# megaduck.net
KiCad netlist of a schematic drawn in EasyEDA Pro
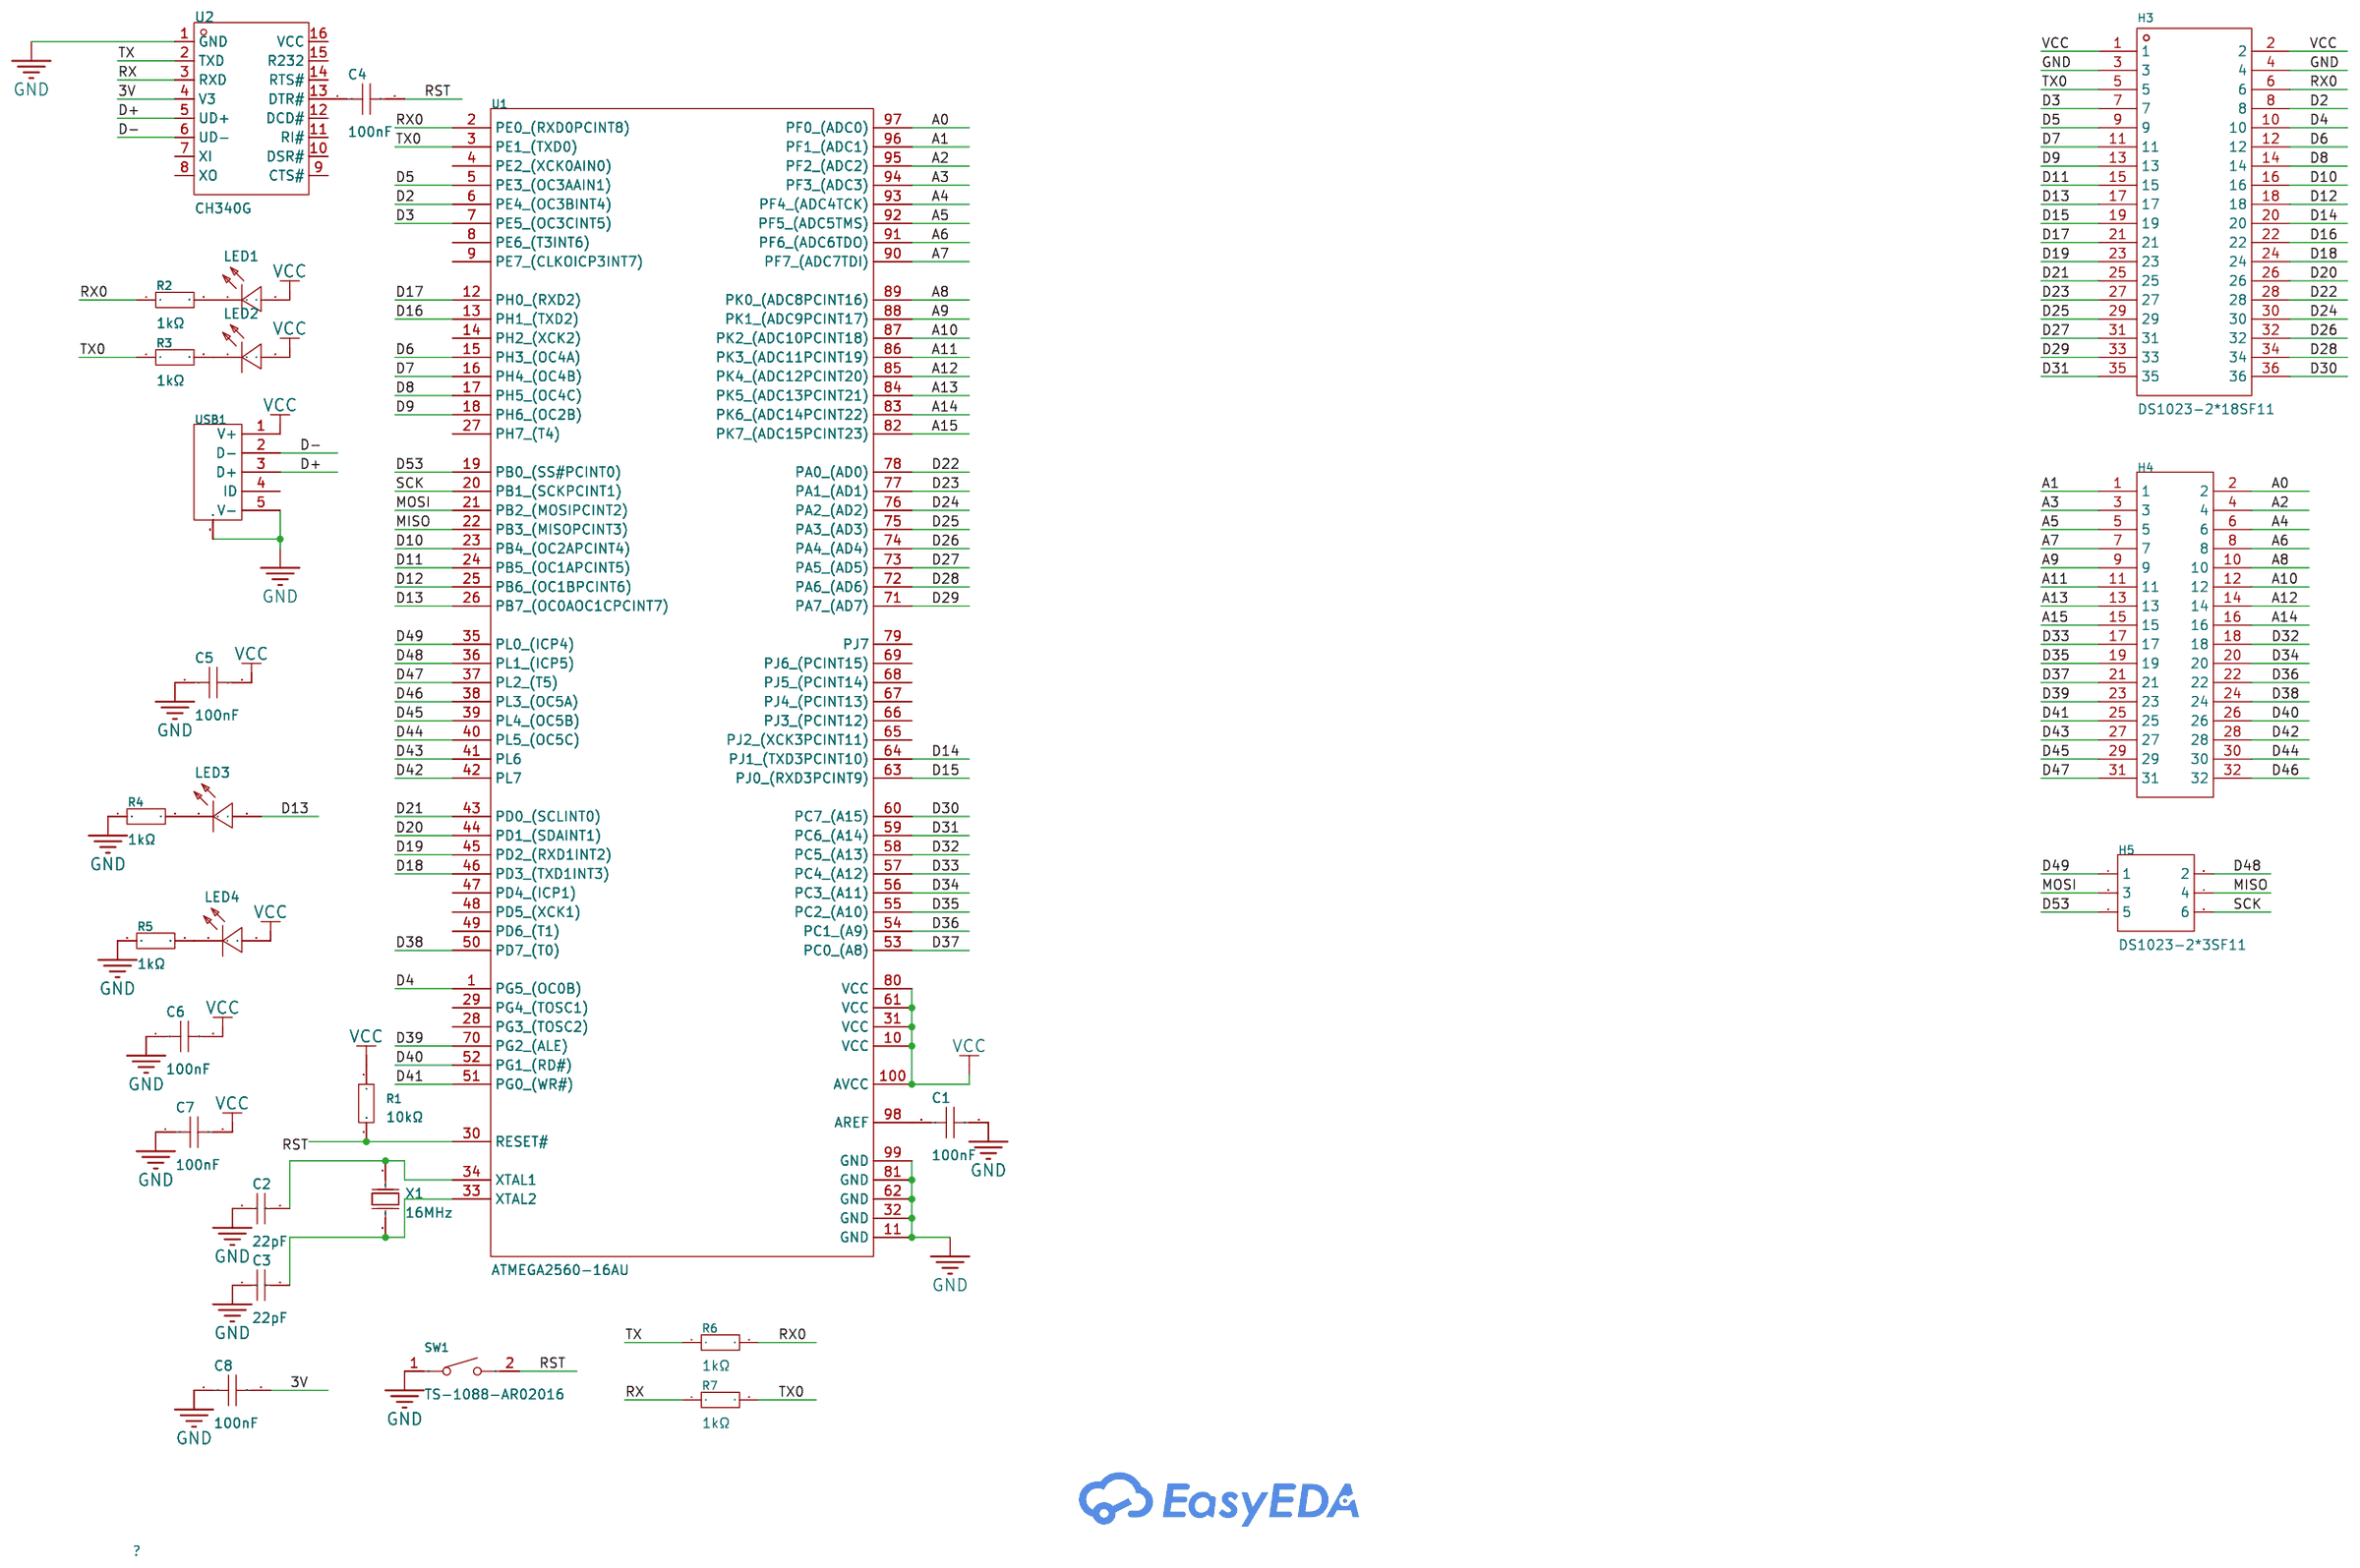
[diagram p0: schematic sheet]

(export (version "E")
  (design (tool "Eeschema 10.0.6"))
  (components
    (comp (ref "C1")
      (value "100nF")
      (footprint "easyedapro:C0402")
      (fields
        (field (name "Manufacturer Part") "CL05B104KO5NNNC")
        (field (name "Manufacturer") "SAMSUNG(三星)")
      )
      (libsource (lib "easyedapro") (part "CL05B104KO5NNNC"))
    )
    (comp (ref "C2")
      (value "22pF")
      (footprint "easyedapro:C0402")
      (fields (field (name "Manufacturer Part") "0402CG220J500NT") (field (name "Manufacturer") "FH(风华)"))
      (libsource (lib "easyedapro") (part "0402CG220J500NT"))
    )
    (comp (ref "C3")
      (value "22pF")
      (footprint "easyedapro:C0402")
      (fields (field (name "Manufacturer Part") "0402CG220J500NT") (field (name "Manufacturer") "FH(风华)"))
      (libsource (lib "easyedapro") (part "0402CG220J500NT"))
    )
    (comp (ref "C4")
      (value "100nF")
      (footprint "easyedapro:C0402")
      (fields
        (field (name "Manufacturer Part") "CL05B104KO5NNNC")
        (field (name "Manufacturer") "SAMSUNG(三星)")
      )
      (libsource (lib "easyedapro") (part "CL05B104KO5NNNC"))
    )
    (comp (ref "C5")
      (value "100nF")
      (footprint "easyedapro:C0402")
      (fields
        (field (name "Manufacturer Part") "CL05B104KO5NNNC")
        (field (name "Manufacturer") "SAMSUNG(三星)")
      )
      (libsource (lib "easyedapro") (part "CL05B104KO5NNNC"))
    )
    (comp (ref "C6")
      (value "100nF")
      (footprint "easyedapro:C0402")
      (fields
        (field (name "Manufacturer Part") "CL05B104KO5NNNC")
        (field (name "Manufacturer") "SAMSUNG(三星)")
      )
      (libsource (lib "easyedapro") (part "CL05B104KO5NNNC"))
    )
    (comp (ref "C7")
      (value "100nF")
      (footprint "easyedapro:C0402")
      (fields
        (field (name "Manufacturer Part") "CL05B104KO5NNNC")
        (field (name "Manufacturer") "SAMSUNG(三星)")
      )
      (libsource (lib "easyedapro") (part "CL05B104KO5NNNC"))
    )
    (comp (ref "C8")
      (value "100nF")
      (footprint "easyedapro:C0402")
      (fields
        (field (name "Manufacturer Part") "CL05B104KO5NNNC")
        (field (name "Manufacturer") "SAMSUNG(三星)")
      )
      (libsource (lib "easyedapro") (part "CL05B104KO5NNNC"))
    )
    (comp (ref "H3")
      (value "DS1023-2*18SF11")
      (footprint "easyedapro:HDR-TH_36P-P2.54-V-F-R2-C18-S2.54-1")
      (fields (field (name "Manufacturer") "CONNFLY"))
      (libsource (lib "easyedapro") (part "DS1023-2*18SF11"))
    )
    (comp (ref "H4")
      (value "DS1023-2*16SF11")
      (footprint "easyedapro:HDR-TH_32P-P2.54-V-F-R2-C16-S2.54-1")
      (fields (field (name "Manufacturer") "CONNFLY"))
      (libsource (lib "easyedapro") (part "DS1023-2*16SF11"))
    )
    (comp (ref "H5")
      (value "DS1023-2*3SF11")
      (footprint "easyedapro:HDR-TH_6P-P2.54-V-F-R2-C3-S2.54")
      (fields (field (name "Manufacturer") "CONNFLY"))
      (libsource (lib "easyedapro") (part "Header-Female-2.54_2x3"))
    )
    (comp (ref "LED1")
      (value "KT-0603R")
      (footprint "easyedapro:LED0603-RD")
      (fields (field (name "Manufacturer") "KENTO"))
      (libsource (lib "easyedapro") (part "KT-0603R"))
    )
    (comp (ref "LED2")
      (value "KT-0603R")
      (footprint "easyedapro:LED0603-RD")
      (fields (field (name "Manufacturer") "KENTO"))
      (libsource (lib "easyedapro") (part "KT-0603R"))
    )
    (comp (ref "LED3")
      (value "KT-0603R")
      (footprint "easyedapro:LED0603-RD")
      (fields (field (name "Manufacturer") "KENTO"))
      (libsource (lib "easyedapro") (part "KT-0603R"))
    )
    (comp (ref "LED4")
      (value "KT-0603R")
      (footprint "easyedapro:LED0603-RD")
      (fields (field (name "Manufacturer") "KENTO"))
      (libsource (lib "easyedapro") (part "KT-0603R"))
    )
    (comp (ref "R1")
      (value "10kΩ")
      (footprint "easyedapro:R1206")
      (fields
        (field (name "Manufacturer Part") "1206W4J0103T5E")
        (field (name "Manufacturer") "UNI-ROYAL(厚声)")
      )
      (libsource (lib "easyedapro") (part "1206W4J0103T5E"))
    )
    (comp (ref "R2")
      (value "1kΩ")
      (footprint "easyedapro:R1206")
      (fields
        (field (name "Manufacturer Part") "1206W4F1001T5E")
        (field (name "Manufacturer") "UNI-ROYAL(厚声)")
      )
      (libsource (lib "easyedapro") (part "1206W4F1001T5E"))
    )
    (comp (ref "R3")
      (value "1kΩ")
      (footprint "easyedapro:R1206")
      (fields
        (field (name "Manufacturer Part") "1206W4F1001T5E")
        (field (name "Manufacturer") "UNI-ROYAL(厚声)")
      )
      (libsource (lib "easyedapro") (part "1206W4F1001T5E"))
    )
    (comp (ref "R4")
      (value "1kΩ")
      (footprint "easyedapro:R1206")
      (fields
        (field (name "Manufacturer Part") "1206W4F1001T5E")
        (field (name "Manufacturer") "UNI-ROYAL(厚声)")
      )
      (libsource (lib "easyedapro") (part "1206W4F1001T5E"))
    )
    (comp (ref "R5")
      (value "1kΩ")
      (footprint "easyedapro:R1206")
      (fields
        (field (name "Manufacturer Part") "1206W4F1001T5E")
        (field (name "Manufacturer") "UNI-ROYAL(厚声)")
      )
      (libsource (lib "easyedapro") (part "1206W4F1001T5E"))
    )
    (comp (ref "R6")
      (value "1kΩ")
      (footprint "easyedapro:R1206")
      (fields
        (field (name "Manufacturer Part") "1206W4F1001T5E")
        (field (name "Manufacturer") "UNI-ROYAL(厚声)")
      )
      (libsource (lib "easyedapro") (part "1206W4F1001T5E"))
    )
    (comp (ref "R7")
      (value "1kΩ")
      (footprint "easyedapro:R1206")
      (fields
        (field (name "Manufacturer Part") "1206W4F1001T5E")
        (field (name "Manufacturer") "UNI-ROYAL(厚声)")
      )
      (libsource (lib "easyedapro") (part "1206W4F1001T5E"))
    )
    (comp (ref "SW1")
      (value "TS-1088-AR02016")
      (footprint "easyedapro:SW-SMD_L3.9-W3.0-P4.45")
      (fields (field (name "Manufacturer") "XUNPU(讯普)"))
      (libsource (lib "easyedapro") (part "TS-1088-AR02016"))
    )
    (comp (ref "U1")
      (value "ATMEGA2560-16AU")
      (footprint "easyedapro:TQFP-100_L14.0-W14.0-P0.50-LS16.0-BL")
      (fields (field (name "Manufacturer") "MICROCHIP(美国微芯)"))
      (libsource (lib "easyedapro") (part "ATMEGA2560-16AU"))
    )
    (comp (ref "U2")
      (value "CH340G")
      (footprint "easyedapro:SOIC-16_L9.9-W3.9-P1.27-LS6.0-BL")
      (fields (field (name "Manufacturer") "WCH(南京沁恒)"))
      (libsource (lib "easyedapro") (part "CH340G"))
    )
    (comp (ref "USB1")
      (value "920-E52A2021S10100")
      (footprint "easyedapro:MICRO-USB-SMD_5P-P0.65-H-F_C10418")
      (fields (field (name "Manufacturer") "精拓金"))
      (libsource (lib "easyedapro") (part "micro USBFemale"))
    )
    (comp (ref "X1")
      (value "16MHz")
      (footprint "easyedapro:HC-49S_L11.4-W4.8")
      (fields (field (name "Manufacturer Part") "X49SM16MSD2SC") (field (name "Manufacturer") "YXC(扬兴晶振)"))
      (libsource (lib "easyedapro") (part "X49SM16MSD2SC"))
    )
  )
  (nets
    (net (code "1") (name "/3V") (class "Default")
      (node (ref "C8") (pin "2") (pinfunction "2_2") (pintype "unspecified"))
      (node (ref "U2") (pin "4") (pinfunction "V3_4") (pintype "unspecified"))
    )
    (net (code "2") (name "/A0") (class "Default")
      (node (ref "H4") (pin "2") (pinfunction "2_2") (pintype "input"))
      (node (ref "U1") (pin "97") (pinfunction "PF0_(ADC0)_97") (pintype "bidirectional"))
    )
    (net (code "3") (name "/A1") (class "Default")
      (node (ref "H4") (pin "1") (pinfunction "1_1") (pintype "input"))
      (node (ref "U1") (pin "96") (pinfunction "PF1_(ADC1)_96") (pintype "bidirectional"))
    )
    (net (code "4") (name "/A2") (class "Default")
      (node (ref "H4") (pin "4") (pinfunction "4_4") (pintype "input"))
      (node (ref "U1") (pin "95") (pinfunction "PF2_(ADC2)_95") (pintype "bidirectional"))
    )
    (net (code "5") (name "/A3") (class "Default")
      (node (ref "H4") (pin "3") (pinfunction "3_3") (pintype "input"))
      (node (ref "U1") (pin "94") (pinfunction "PF3_(ADC3)_94") (pintype "bidirectional"))
    )
    (net (code "6") (name "/A4") (class "Default")
      (node (ref "H4") (pin "6") (pinfunction "6_6") (pintype "input"))
      (node (ref "U1") (pin "93") (pinfunction "PF4_(ADC4TCK)_93") (pintype "bidirectional"))
    )
    (net (code "7") (name "/A5") (class "Default")
      (node (ref "H4") (pin "5") (pinfunction "5_5") (pintype "input"))
      (node (ref "U1") (pin "92") (pinfunction "PF5_(ADC5TMS)_92") (pintype "bidirectional"))
    )
    (net (code "8") (name "/A6") (class "Default")
      (node (ref "H4") (pin "8") (pinfunction "8_8") (pintype "input"))
      (node (ref "U1") (pin "91") (pinfunction "PF6_(ADC6TDO)_91") (pintype "bidirectional"))
    )
    (net (code "9") (name "/A7") (class "Default")
      (node (ref "H4") (pin "7") (pinfunction "7_7") (pintype "input"))
      (node (ref "U1") (pin "90") (pinfunction "PF7_(ADC7TDI)_90") (pintype "bidirectional"))
    )
    (net (code "10") (name "/A8") (class "Default")
      (node (ref "H4") (pin "10") (pinfunction "10_10") (pintype "input"))
      (node (ref "U1") (pin "89") (pinfunction "PK0_(ADC8PCINT16)_89") (pintype "bidirectional"))
    )
    (net (code "11") (name "/A9") (class "Default")
      (node (ref "H4") (pin "9") (pinfunction "9_9") (pintype "input"))
      (node (ref "U1") (pin "88") (pinfunction "PK1_(ADC9PCINT17)_88") (pintype "bidirectional"))
    )
    (net (code "12") (name "/A10") (class "Default")
      (node (ref "H4") (pin "12") (pinfunction "12_12") (pintype "input"))
      (node (ref "U1") (pin "87") (pinfunction "PK2_(ADC10PCINT18)_87") (pintype "bidirectional"))
    )
    (net (code "13") (name "/A11") (class "Default")
      (node (ref "H4") (pin "11") (pinfunction "11_11") (pintype "input"))
      (node (ref "U1") (pin "86") (pinfunction "PK3_(ADC11PCINT19)_86") (pintype "bidirectional"))
    )
    (net (code "14") (name "/A12") (class "Default")
      (node (ref "H4") (pin "14") (pinfunction "14_14") (pintype "input"))
      (node (ref "U1") (pin "85") (pinfunction "PK4_(ADC12PCINT20)_85") (pintype "bidirectional"))
    )
    (net (code "15") (name "/A13") (class "Default")
      (node (ref "H4") (pin "13") (pinfunction "13_13") (pintype "input"))
      (node (ref "U1") (pin "84") (pinfunction "PK5_(ADC13PCINT21)_84") (pintype "bidirectional"))
    )
    (net (code "16") (name "/A14") (class "Default")
      (node (ref "H4") (pin "16") (pinfunction "16_16") (pintype "input"))
      (node (ref "U1") (pin "83") (pinfunction "PK6_(ADC14PCINT22)_83") (pintype "bidirectional"))
    )
    (net (code "17") (name "/A15") (class "Default")
      (node (ref "H4") (pin "15") (pinfunction "15_15") (pintype "input"))
      (node (ref "U1") (pin "82") (pinfunction "PK7_(ADC15PCINT23)_82") (pintype "bidirectional"))
    )
    (net (code "18") (name "/D+") (class "Default")
      (node (ref "U2") (pin "5") (pinfunction "UD+_5") (pintype "unspecified"))
      (node (ref "USB1") (pin "3") (pinfunction "D+_3") (pintype "input"))
    )
    (net (code "19") (name "/D-") (class "Default")
      (node (ref "U2") (pin "6") (pinfunction "UD-_6") (pintype "unspecified"))
      (node (ref "USB1") (pin "2") (pinfunction "D-_2") (pintype "input"))
    )
    (net (code "20") (name "/D2") (class "Default")
      (node (ref "H3") (pin "8") (pinfunction "8_8") (pintype "input"))
      (node (ref "U1") (pin "6") (pinfunction "PE4_(OC3BINT4)_6") (pintype "bidirectional"))
    )
    (net (code "21") (name "/D3") (class "Default")
      (node (ref "H3") (pin "7") (pinfunction "7_7") (pintype "input"))
      (node (ref "U1") (pin "7") (pinfunction "PE5_(OC3CINT5)_7") (pintype "bidirectional"))
    )
    (net (code "22") (name "/D4") (class "Default")
      (node (ref "H3") (pin "10") (pinfunction "10_10") (pintype "input"))
      (node (ref "U1") (pin "1") (pinfunction "PG5_(OC0B)_1") (pintype "bidirectional"))
    )
    (net (code "23") (name "/D5") (class "Default")
      (node (ref "H3") (pin "9") (pinfunction "9_9") (pintype "input"))
      (node (ref "U1") (pin "5") (pinfunction "PE3_(OC3AAIN1)_5") (pintype "bidirectional"))
    )
    (net (code "24") (name "/D6") (class "Default")
      (node (ref "H3") (pin "12") (pinfunction "12_12") (pintype "input"))
      (node (ref "U1") (pin "15") (pinfunction "PH3_(OC4A)_15") (pintype "bidirectional"))
    )
    (net (code "25") (name "/D7") (class "Default")
      (node (ref "H3") (pin "11") (pinfunction "11_11") (pintype "input"))
      (node (ref "U1") (pin "16") (pinfunction "PH4_(OC4B)_16") (pintype "bidirectional"))
    )
    (net (code "26") (name "/D8") (class "Default")
      (node (ref "H3") (pin "14") (pinfunction "14_14") (pintype "input"))
      (node (ref "U1") (pin "17") (pinfunction "PH5_(OC4C)_17") (pintype "bidirectional"))
    )
    (net (code "27") (name "/D9") (class "Default")
      (node (ref "H3") (pin "13") (pinfunction "13_13") (pintype "input"))
      (node (ref "U1") (pin "18") (pinfunction "PH6_(OC2B)_18") (pintype "bidirectional"))
    )
    (net (code "28") (name "/D10") (class "Default")
      (node (ref "H3") (pin "16") (pinfunction "16_16") (pintype "input"))
      (node (ref "U1") (pin "23") (pinfunction "PB4_(OC2APCINT4)_23") (pintype "bidirectional"))
    )
    (net (code "29") (name "/D11") (class "Default")
      (node (ref "H3") (pin "15") (pinfunction "15_15") (pintype "input"))
      (node (ref "U1") (pin "24") (pinfunction "PB5_(OC1APCINT5)_24") (pintype "bidirectional"))
    )
    (net (code "30") (name "/D12") (class "Default")
      (node (ref "H3") (pin "18") (pinfunction "18_18") (pintype "input"))
      (node (ref "U1") (pin "25") (pinfunction "PB6_(OC1BPCINT6)_25") (pintype "bidirectional"))
    )
    (net (code "31") (name "/D13") (class "Default")
      (node (ref "H3") (pin "17") (pinfunction "17_17") (pintype "input"))
      (node (ref "LED3") (pin "2") (pinfunction "A_2") (pintype "unspecified"))
      (node (ref "U1") (pin "26") (pinfunction "PB7_(OC0AOC1CPCINT7)_26") (pintype "bidirectional"))
    )
    (net (code "32") (name "/D14") (class "Default")
      (node (ref "H3") (pin "20") (pinfunction "20_20") (pintype "input"))
      (node (ref "U1") (pin "64") (pinfunction "PJ1_(TXD3PCINT10)_64") (pintype "bidirectional"))
    )
    (net (code "33") (name "/D15") (class "Default")
      (node (ref "H3") (pin "19") (pinfunction "19_19") (pintype "input"))
      (node (ref "U1") (pin "63") (pinfunction "PJ0_(RXD3PCINT9)_63") (pintype "bidirectional"))
    )
    (net (code "34") (name "/D16") (class "Default")
      (node (ref "H3") (pin "22") (pinfunction "22_22") (pintype "input"))
      (node (ref "U1") (pin "13") (pinfunction "PH1_(TXD2)_13") (pintype "bidirectional"))
    )
    (net (code "35") (name "/D17") (class "Default")
      (node (ref "H3") (pin "21") (pinfunction "21_21") (pintype "input"))
      (node (ref "U1") (pin "12") (pinfunction "PH0_(RXD2)_12") (pintype "bidirectional"))
    )
    (net (code "36") (name "/D18") (class "Default")
      (node (ref "H3") (pin "24") (pinfunction "24_24") (pintype "input"))
      (node (ref "U1") (pin "46") (pinfunction "PD3_(TXD1INT3)_46") (pintype "bidirectional"))
    )
    (net (code "37") (name "/D19") (class "Default")
      (node (ref "H3") (pin "23") (pinfunction "23_23") (pintype "input"))
      (node (ref "U1") (pin "45") (pinfunction "PD2_(RXD1INT2)_45") (pintype "bidirectional"))
    )
    (net (code "38") (name "/D20") (class "Default")
      (node (ref "H3") (pin "26") (pinfunction "26_26") (pintype "input"))
      (node (ref "U1") (pin "44") (pinfunction "PD1_(SDAINT1)_44") (pintype "bidirectional"))
    )
    (net (code "39") (name "/D21") (class "Default")
      (node (ref "H3") (pin "25") (pinfunction "25_25") (pintype "input"))
      (node (ref "U1") (pin "43") (pinfunction "PD0_(SCLINT0)_43") (pintype "bidirectional"))
    )
    (net (code "40") (name "/D22") (class "Default")
      (node (ref "H3") (pin "28") (pinfunction "28_28") (pintype "input"))
      (node (ref "U1") (pin "78") (pinfunction "PA0_(AD0)_78") (pintype "bidirectional"))
    )
    (net (code "41") (name "/D23") (class "Default")
      (node (ref "H3") (pin "27") (pinfunction "27_27") (pintype "input"))
      (node (ref "U1") (pin "77") (pinfunction "PA1_(AD1)_77") (pintype "bidirectional"))
    )
    (net (code "42") (name "/D24") (class "Default")
      (node (ref "H3") (pin "30") (pinfunction "30_30") (pintype "input"))
      (node (ref "U1") (pin "76") (pinfunction "PA2_(AD2)_76") (pintype "bidirectional"))
    )
    (net (code "43") (name "/D25") (class "Default")
      (node (ref "H3") (pin "29") (pinfunction "29_29") (pintype "input"))
      (node (ref "U1") (pin "75") (pinfunction "PA3_(AD3)_75") (pintype "bidirectional"))
    )
    (net (code "44") (name "/D26") (class "Default")
      (node (ref "H3") (pin "32") (pinfunction "32_32") (pintype "input"))
      (node (ref "U1") (pin "74") (pinfunction "PA4_(AD4)_74") (pintype "bidirectional"))
    )
    (net (code "45") (name "/D27") (class "Default")
      (node (ref "H3") (pin "31") (pinfunction "31_31") (pintype "input"))
      (node (ref "U1") (pin "73") (pinfunction "PA5_(AD5)_73") (pintype "bidirectional"))
    )
    (net (code "46") (name "/D28") (class "Default")
      (node (ref "H3") (pin "34") (pinfunction "34_34") (pintype "input"))
      (node (ref "U1") (pin "72") (pinfunction "PA6_(AD6)_72") (pintype "bidirectional"))
    )
    (net (code "47") (name "/D29") (class "Default")
      (node (ref "H3") (pin "33") (pinfunction "33_33") (pintype "input"))
      (node (ref "U1") (pin "71") (pinfunction "PA7_(AD7)_71") (pintype "bidirectional"))
    )
    (net (code "48") (name "/D30") (class "Default")
      (node (ref "H3") (pin "36") (pinfunction "36_36") (pintype "input"))
      (node (ref "U1") (pin "60") (pinfunction "PC7_(A15)_60") (pintype "bidirectional"))
    )
    (net (code "49") (name "/D31") (class "Default")
      (node (ref "H3") (pin "35") (pinfunction "35_35") (pintype "input"))
      (node (ref "U1") (pin "59") (pinfunction "PC6_(A14)_59") (pintype "bidirectional"))
    )
    (net (code "50") (name "/D32") (class "Default")
      (node (ref "H4") (pin "18") (pinfunction "18_18") (pintype "input"))
      (node (ref "U1") (pin "58") (pinfunction "PC5_(A13)_58") (pintype "bidirectional"))
    )
    (net (code "51") (name "/D33") (class "Default")
      (node (ref "H4") (pin "17") (pinfunction "17_17") (pintype "input"))
      (node (ref "U1") (pin "57") (pinfunction "PC4_(A12)_57") (pintype "bidirectional"))
    )
    (net (code "52") (name "/D34") (class "Default")
      (node (ref "H4") (pin "20") (pinfunction "20_20") (pintype "input"))
      (node (ref "U1") (pin "56") (pinfunction "PC3_(A11)_56") (pintype "bidirectional"))
    )
    (net (code "53") (name "/D35") (class "Default")
      (node (ref "H4") (pin "19") (pinfunction "19_19") (pintype "input"))
      (node (ref "U1") (pin "55") (pinfunction "PC2_(A10)_55") (pintype "bidirectional"))
    )
    (net (code "54") (name "/D36") (class "Default")
      (node (ref "H4") (pin "22") (pinfunction "22_22") (pintype "input"))
      (node (ref "U1") (pin "54") (pinfunction "PC1_(A9)_54") (pintype "bidirectional"))
    )
    (net (code "55") (name "/D37") (class "Default")
      (node (ref "H4") (pin "21") (pinfunction "21_21") (pintype "input"))
      (node (ref "U1") (pin "53") (pinfunction "PC0_(A8)_53") (pintype "bidirectional"))
    )
    (net (code "56") (name "/D38") (class "Default")
      (node (ref "H4") (pin "24") (pinfunction "24_24") (pintype "input"))
      (node (ref "U1") (pin "50") (pinfunction "PD7_(T0)_50") (pintype "bidirectional"))
    )
    (net (code "57") (name "/D39") (class "Default")
      (node (ref "H4") (pin "23") (pinfunction "23_23") (pintype "input"))
      (node (ref "U1") (pin "70") (pinfunction "PG2_(ALE)_70") (pintype "bidirectional"))
    )
    (net (code "58") (name "/D40") (class "Default")
      (node (ref "H4") (pin "26") (pinfunction "26_26") (pintype "input"))
      (node (ref "U1") (pin "52") (pinfunction "PG1_(RD#)_52") (pintype "bidirectional"))
    )
    (net (code "59") (name "/D41") (class "Default")
      (node (ref "H4") (pin "25") (pinfunction "25_25") (pintype "input"))
      (node (ref "U1") (pin "51") (pinfunction "PG0_(WR#)_51") (pintype "bidirectional"))
    )
    (net (code "60") (name "/D42") (class "Default")
      (node (ref "H4") (pin "28") (pinfunction "28_28") (pintype "input"))
      (node (ref "U1") (pin "42") (pinfunction "PL7_42") (pintype "bidirectional"))
    )
    (net (code "61") (name "/D43") (class "Default")
      (node (ref "H4") (pin "27") (pinfunction "27_27") (pintype "input"))
      (node (ref "U1") (pin "41") (pinfunction "PL6_41") (pintype "bidirectional"))
    )
    (net (code "62") (name "/D44") (class "Default")
      (node (ref "H4") (pin "30") (pinfunction "30_30") (pintype "input"))
      (node (ref "U1") (pin "40") (pinfunction "PL5_(OC5C)_40") (pintype "bidirectional"))
    )
    (net (code "63") (name "/D45") (class "Default")
      (node (ref "H4") (pin "29") (pinfunction "29_29") (pintype "input"))
      (node (ref "U1") (pin "39") (pinfunction "PL4_(OC5B)_39") (pintype "bidirectional"))
    )
    (net (code "64") (name "/D46") (class "Default")
      (node (ref "H4") (pin "32") (pinfunction "32_32") (pintype "input"))
      (node (ref "U1") (pin "38") (pinfunction "PL3_(OC5A)_38") (pintype "bidirectional"))
    )
    (net (code "65") (name "/D47") (class "Default")
      (node (ref "H4") (pin "31") (pinfunction "31_31") (pintype "input"))
      (node (ref "U1") (pin "37") (pinfunction "PL2_(T5)_37") (pintype "bidirectional"))
    )
    (net (code "66") (name "/D48") (class "Default")
      (node (ref "H5") (pin "2") (pinfunction "2_2") (pintype "input"))
      (node (ref "U1") (pin "36") (pinfunction "PL1_(ICP5)_36") (pintype "bidirectional"))
    )
    (net (code "67") (name "/D49") (class "Default")
      (node (ref "H5") (pin "1") (pinfunction "1_1") (pintype "input"))
      (node (ref "U1") (pin "35") (pinfunction "PL0_(ICP4)_35") (pintype "bidirectional"))
    )
    (net (code "68") (name "/D53") (class "Default")
      (node (ref "H5") (pin "5") (pinfunction "5_5") (pintype "input"))
      (node (ref "U1") (pin "19") (pinfunction "PB0_(SS#PCINT0)_19") (pintype "bidirectional"))
    )
    (net (code "69") (name "/MISO") (class "Default")
      (node (ref "H5") (pin "4") (pinfunction "4_4") (pintype "input"))
      (node (ref "U1") (pin "22") (pinfunction "PB3_(MISOPCINT3)_22") (pintype "bidirectional"))
    )
    (net (code "70") (name "/MOSI") (class "Default")
      (node (ref "H5") (pin "3") (pinfunction "3_3") (pintype "input"))
      (node (ref "U1") (pin "21") (pinfunction "PB2_(MOSIPCINT2)_21") (pintype "bidirectional"))
    )
    (net (code "71") (name "/RST") (class "Default")
      (node (ref "C4") (pin "2") (pinfunction "2_2") (pintype "unspecified"))
      (node (ref "R1") (pin "2") (pinfunction "2_2") (pintype "input"))
      (node (ref "SW1") (pin "2") (pinfunction "2_2") (pintype "input"))
      (node (ref "U1") (pin "30") (pinfunction "RESET#_30") (pintype "input"))
    )
    (net (code "72") (name "/RX") (class "Default")
      (node (ref "R7") (pin "1") (pinfunction "1_1") (pintype "input"))
      (node (ref "U2") (pin "3") (pinfunction "RXD_3") (pintype "unspecified"))
    )
    (net (code "73") (name "/RX0") (class "Default")
      (node (ref "H3") (pin "6") (pinfunction "6_6") (pintype "input"))
      (node (ref "R2") (pin "1") (pinfunction "1_1") (pintype "input"))
      (node (ref "R6") (pin "2") (pinfunction "2_2") (pintype "input"))
      (node (ref "U1") (pin "2") (pinfunction "PE0_(RXD0PCINT8)_2") (pintype "bidirectional"))
    )
    (net (code "74") (name "/SCK") (class "Default")
      (node (ref "H5") (pin "6") (pinfunction "6_6") (pintype "input"))
      (node (ref "U1") (pin "20") (pinfunction "PB1_(SCKPCINT1)_20") (pintype "bidirectional"))
    )
    (net (code "75") (name "/TX") (class "Default")
      (node (ref "R6") (pin "1") (pinfunction "1_1") (pintype "input"))
      (node (ref "U2") (pin "2") (pinfunction "TXD_2") (pintype "unspecified"))
    )
    (net (code "76") (name "/TX0") (class "Default")
      (node (ref "H3") (pin "5") (pinfunction "5_5") (pintype "input"))
      (node (ref "R3") (pin "1") (pinfunction "1_1") (pintype "input"))
      (node (ref "R7") (pin "2") (pinfunction "2_2") (pintype "input"))
      (node (ref "U1") (pin "3") (pinfunction "PE1_(TXD0)_3") (pintype "bidirectional"))
    )
    (net (code "77") (name "GND") (class "Default")
      (node (ref "C1") (pin "2") (pinfunction "2_2") (pintype "unspecified"))
      (node (ref "C2") (pin "1") (pinfunction "1_1") (pintype "input"))
      (node (ref "C3") (pin "1") (pinfunction "1_1") (pintype "input"))
      (node (ref "C5") (pin "1") (pinfunction "1_1") (pintype "unspecified"))
      (node (ref "C6") (pin "1") (pinfunction "1_1") (pintype "unspecified"))
      (node (ref "C7") (pin "1") (pinfunction "1_1") (pintype "unspecified"))
      (node (ref "C8") (pin "1") (pinfunction "1_1") (pintype "unspecified"))
      (node (ref "H3") (pin "3") (pinfunction "3_3") (pintype "input"))
      (node (ref "H3") (pin "4") (pinfunction "4_4") (pintype "input"))
      (node (ref "R4") (pin "1") (pinfunction "1_1") (pintype "input"))
      (node (ref "R5") (pin "1") (pinfunction "1_1") (pintype "input"))
      (node (ref "SW1") (pin "1") (pinfunction "1_1") (pintype "input"))
      (node (ref "U1") (pin "11") (pinfunction "GND_11") (pintype "input"))
      (node (ref "U1") (pin "32") (pinfunction "GND_32") (pintype "input"))
      (node (ref "U1") (pin "62") (pinfunction "GND_62") (pintype "input"))
      (node (ref "U1") (pin "81") (pinfunction "GND_81") (pintype "input"))
      (node (ref "U1") (pin "99") (pinfunction "GND_99") (pintype "input"))
      (node (ref "U2") (pin "1") (pinfunction "GND_1") (pintype "unspecified"))
      (node (ref "USB1") (pin "5") (pinfunction "V-_5") (pintype "input"))
      (node (ref "USB1") (pin "SH0") (pinfunction "MTN_SH0") (pintype "input"))
      (node (ref "USB1") (pin "SH1") (pinfunction "1_SH1") (pintype "input"))
      (node (ref "USB1") (pin "SH2") (pinfunction "2_SH2") (pintype "input"))
      (node (ref "USB1") (pin "SH3") (pinfunction "3_SH3") (pintype "input"))
    )
    (net (code "78") (name "Net-(LED1-K)") (class "Default")
      (node (ref "LED1") (pin "1") (pinfunction "K_1") (pintype "unspecified"))
      (node (ref "R2") (pin "2") (pinfunction "2_2") (pintype "input"))
    )
    (net (code "79") (name "Net-(LED2-K)") (class "Default")
      (node (ref "LED2") (pin "1") (pinfunction "K_1") (pintype "unspecified"))
      (node (ref "R3") (pin "2") (pinfunction "2_2") (pintype "input"))
    )
    (net (code "80") (name "Net-(LED3-K)") (class "Default")
      (node (ref "LED3") (pin "1") (pinfunction "K_1") (pintype "unspecified"))
      (node (ref "R4") (pin "2") (pinfunction "2_2") (pintype "input"))
    )
    (net (code "81") (name "Net-(LED4-K)") (class "Default")
      (node (ref "LED4") (pin "1") (pinfunction "K_1") (pintype "unspecified"))
      (node (ref "R5") (pin "2") (pinfunction "2_2") (pintype "input"))
    )
    (net (code "82") (name "Net-(U1-AREF)") (class "Default")
      (node (ref "C1") (pin "1") (pinfunction "1_1") (pintype "unspecified"))
      (node (ref "U1") (pin "98") (pinfunction "AREF_98") (pintype "input"))
    )
    (net (code "83") (name "Net-(U1-XTAL1)") (class "Default")
      (node (ref "C2") (pin "2") (pinfunction "2_2") (pintype "input"))
      (node (ref "U1") (pin "34") (pinfunction "XTAL1_34") (pintype "input"))
      (node (ref "X1") (pin "1") (pinfunction "OSC1_1") (pintype "input"))
    )
    (net (code "84") (name "Net-(U1-XTAL2)") (class "Default")
      (node (ref "C3") (pin "2") (pinfunction "2_2") (pintype "input"))
      (node (ref "U1") (pin "33") (pinfunction "XTAL2_33") (pintype "output"))
      (node (ref "X1") (pin "2") (pinfunction "OSC2_2") (pintype "input"))
    )
    (net (code "85") (name "Net-(U2-DTR#)") (class "Default")
      (node (ref "C4") (pin "1") (pinfunction "1_1") (pintype "unspecified"))
      (node (ref "U2") (pin "13") (pinfunction "DTR#_13") (pintype "unspecified"))
    )
    (net (code "86") (name "VCC") (class "Default")
      (node (ref "C5") (pin "2") (pinfunction "2_2") (pintype "unspecified"))
      (node (ref "C6") (pin "2") (pinfunction "2_2") (pintype "unspecified"))
      (node (ref "C7") (pin "2") (pinfunction "2_2") (pintype "unspecified"))
      (node (ref "H3") (pin "1") (pinfunction "1_1") (pintype "input"))
      (node (ref "H3") (pin "2") (pinfunction "2_2") (pintype "input"))
      (node (ref "LED1") (pin "2") (pinfunction "A_2") (pintype "unspecified"))
      (node (ref "LED2") (pin "2") (pinfunction "A_2") (pintype "unspecified"))
      (node (ref "LED4") (pin "2") (pinfunction "A_2") (pintype "unspecified"))
      (node (ref "R1") (pin "1") (pinfunction "1_1") (pintype "input"))
      (node (ref "U1") (pin "10") (pinfunction "VCC_10") (pintype "input"))
      (node (ref "U1") (pin "100") (pinfunction "AVCC_100") (pintype "input"))
      (node (ref "U1") (pin "31") (pinfunction "VCC_31") (pintype "input"))
      (node (ref "U1") (pin "61") (pinfunction "VCC_61") (pintype "input"))
      (node (ref "U1") (pin "80") (pinfunction "VCC_80") (pintype "input"))
      (node (ref "USB1") (pin "1") (pinfunction "V+_1") (pintype "input"))
    )
    (net (code "87") (name "unconnected-(U1-PD4_(ICP1)-Pad47)") (class "Default")
      (node (ref "U1") (pin "47") (pinfunction "PD4_(ICP1)_47") (pintype "bidirectional"))
    )
    (net (code "88") (name "unconnected-(U1-PD5_(XCK1)-Pad48)") (class "Default")
      (node (ref "U1") (pin "48") (pinfunction "PD5_(XCK1)_48") (pintype "bidirectional"))
    )
    (net (code "89") (name "unconnected-(U1-PD6_(T1)-Pad49)") (class "Default")
      (node (ref "U1") (pin "49") (pinfunction "PD6_(T1)_49") (pintype "bidirectional"))
    )
    (net (code "90") (name "unconnected-(U1-PE2_(XCK0AIN0)-Pad4)") (class "Default")
      (node (ref "U1") (pin "4") (pinfunction "PE2_(XCK0AIN0)_4") (pintype "bidirectional"))
    )
    (net (code "91") (name "unconnected-(U1-PE6_(T3INT6)-Pad8)") (class "Default")
      (node (ref "U1") (pin "8") (pinfunction "PE6_(T3INT6)_8") (pintype "bidirectional"))
    )
    (net (code "92") (name "unconnected-(U1-PE7_(CLKOICP3INT7)-Pad9)") (class "Default")
      (node (ref "U1") (pin "9") (pinfunction "PE7_(CLKOICP3INT7)_9") (pintype "bidirectional"))
    )
    (net (code "93") (name "unconnected-(U1-PG3_(TOSC2)-Pad28)") (class "Default")
      (node (ref "U1") (pin "28") (pinfunction "PG3_(TOSC2)_28") (pintype "bidirectional"))
    )
    (net (code "94") (name "unconnected-(U1-PG4_(TOSC1)-Pad29)") (class "Default")
      (node (ref "U1") (pin "29") (pinfunction "PG4_(TOSC1)_29") (pintype "bidirectional"))
    )
    (net (code "95") (name "unconnected-(U1-PH2_(XCK2)-Pad14)") (class "Default")
      (node (ref "U1") (pin "14") (pinfunction "PH2_(XCK2)_14") (pintype "bidirectional"))
    )
    (net (code "96") (name "unconnected-(U1-PH7_(T4)-Pad27)") (class "Default")
      (node (ref "U1") (pin "27") (pinfunction "PH7_(T4)_27") (pintype "bidirectional"))
    )
    (net (code "97") (name "unconnected-(U1-PJ2_(XCK3PCINT11)-Pad65)") (class "Default")
      (node (ref "U1") (pin "65") (pinfunction "PJ2_(XCK3PCINT11)_65") (pintype "bidirectional"))
    )
    (net (code "98") (name "unconnected-(U1-PJ3_(PCINT12)-Pad66)") (class "Default")
      (node (ref "U1") (pin "66") (pinfunction "PJ3_(PCINT12)_66") (pintype "bidirectional"))
    )
    (net (code "99") (name "unconnected-(U1-PJ4_(PCINT13)-Pad67)") (class "Default")
      (node (ref "U1") (pin "67") (pinfunction "PJ4_(PCINT13)_67") (pintype "bidirectional"))
    )
    (net (code "100") (name "unconnected-(U1-PJ5_(PCINT14)-Pad68)") (class "Default")
      (node (ref "U1") (pin "68") (pinfunction "PJ5_(PCINT14)_68") (pintype "bidirectional"))
    )
    (net (code "101") (name "unconnected-(U1-PJ6_(PCINT15)-Pad69)") (class "Default")
      (node (ref "U1") (pin "69") (pinfunction "PJ6_(PCINT15)_69") (pintype "bidirectional"))
    )
    (net (code "102") (name "unconnected-(U1-PJ7-Pad79)") (class "Default")
      (node (ref "U1") (pin "79") (pinfunction "PJ7_79") (pintype "bidirectional"))
    )
    (net (code "103") (name "unconnected-(U2-CTS#-Pad9)") (class "Default")
      (node (ref "U2") (pin "9") (pinfunction "CTS#_9") (pintype "unspecified"))
    )
    (net (code "104") (name "unconnected-(U2-DCD#-Pad12)") (class "Default")
      (node (ref "U2") (pin "12") (pinfunction "DCD#_12") (pintype "unspecified"))
    )
    (net (code "105") (name "unconnected-(U2-DSR#-Pad10)") (class "Default")
      (node (ref "U2") (pin "10") (pinfunction "DSR#_10") (pintype "unspecified"))
    )
    (net (code "106") (name "unconnected-(U2-R232-Pad15)") (class "Default")
      (node (ref "U2") (pin "15") (pinfunction "R232_15") (pintype "unspecified"))
    )
    (net (code "107") (name "unconnected-(U2-RI#-Pad11)") (class "Default")
      (node (ref "U2") (pin "11") (pinfunction "RI#_11") (pintype "unspecified"))
    )
    (net (code "108") (name "unconnected-(U2-RTS#-Pad14)") (class "Default")
      (node (ref "U2") (pin "14") (pinfunction "RTS#_14") (pintype "unspecified"))
    )
    (net (code "109") (name "unconnected-(U2-VCC-Pad16)") (class "Default")
      (node (ref "U2") (pin "16") (pinfunction "VCC_16") (pintype "unspecified"))
    )
    (net (code "110") (name "unconnected-(U2-XI-Pad7)") (class "Default")
      (node (ref "U2") (pin "7") (pinfunction "XI_7") (pintype "unspecified"))
    )
    (net (code "111") (name "unconnected-(U2-XO-Pad8)") (class "Default")
      (node (ref "U2") (pin "8") (pinfunction "XO_8") (pintype "unspecified"))
    )
    (net (code "112") (name "unconnected-(USB1-ID-Pad4)") (class "Default")
      (node (ref "USB1") (pin "4") (pinfunction "ID_4") (pintype "input"))
    )
  )
)
